# Enclosure_100x68_PBC-X.net
KiCad netlist of a schematic drawn in EAGLE
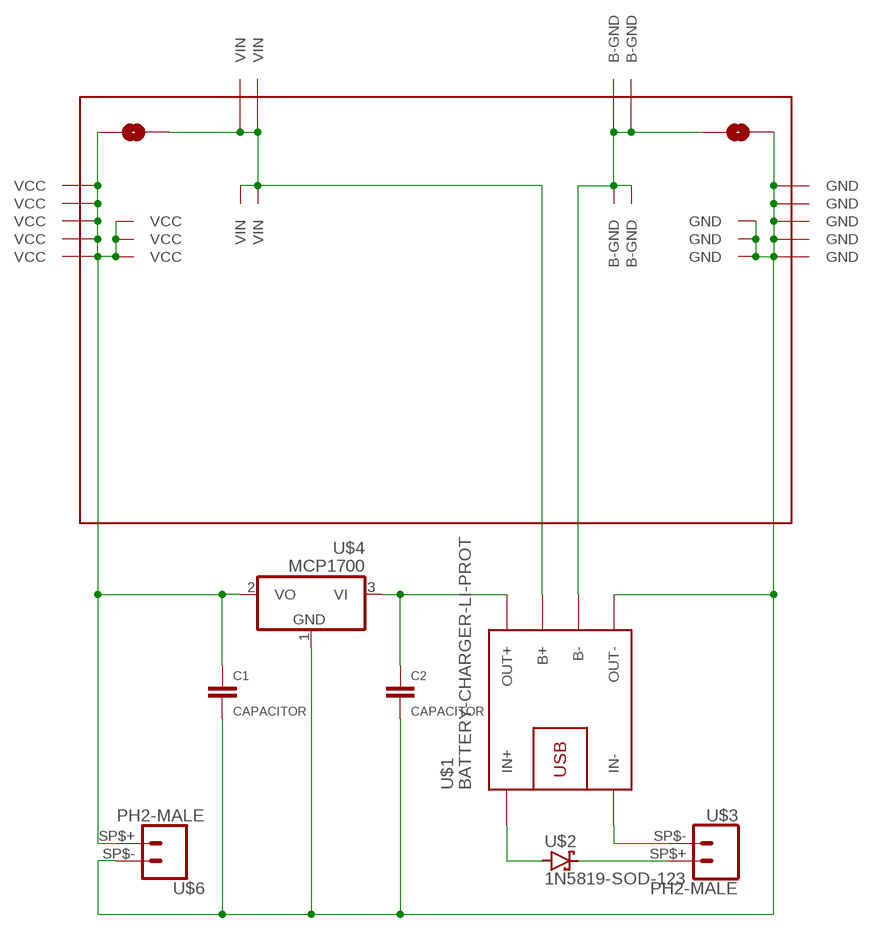
[diagram p0: schematic, sheet 1]

(export (version "E")
  (design (tool "Eeschema 10.0.6"))
  (components
    (comp (ref "C1")
      (value "CAPACITOR")
      (footprint "eagle-import:C0805")
      (libsource (lib "eagle-import") (part "CAPACITOR"))
    )
    (comp (ref "C2")
      (value "CAPACITOR")
      (footprint "eagle-import:C0805")
      (libsource (lib "eagle-import") (part "CAPACITOR"))
    )
    (comp (ref "U$1")
      (value "BATTERY-CHARGER-LI-PROT")
      (footprint "eagle-import:BATTERY-CHARGER-LI-PROT")
      (libsource (lib "eagle-import") (part "BATTERY-CHARGER-LI-PROT"))
    )
    (comp (ref "U$2")
      (value "1N5819-SOD-123")
      (footprint "eagle-import:SOD-123")
      (libsource (lib "eagle-import") (part "1N5819-SOD-123"))
    )
    (comp (ref "U$3")
      (value "PH2-MALE")
      (footprint "eagle-import:PH2")
      (libsource (lib "eagle-import") (part "PH2-MALE"))
    )
    (comp (ref "U$4")
      (value "MCP1700")
      (footprint "eagle-import:SOT23")
      (libsource (lib "eagle-import") (part "MCP1700"))
    )
    (comp (ref "U$5")
      (value "PROTO-34X22-BAT-SJ-CHG")
      (footprint "eagle-import:PROTO-34X22-BAT-SJ-CHG")
      (libsource (lib "eagle-import") (part "PROTO-34X22-BAT-SJ-CHG"))
    )
    (comp (ref "U$6")
      (value "PH2-MALE")
      (footprint "eagle-import:PH2")
      (libsource (lib "eagle-import") (part "PH2-MALE"))
    )
  )
  (nets
    (net (code "1") (name "Net-(U$1-PadB+)") (class "Default")
      (node (ref "U$1") (pin "B+") (pinfunction "B+_B+") (pintype "bidirectional"))
      (node (ref "U$5") (pin "P02-17") (pinfunction "VIN_P02-17") (pintype "power_in"))
      (node (ref "U$5") (pin "P03-16") (pinfunction "VIN_P03-16") (pintype "power_in"))
      (node (ref "U$5") (pin "P05-19") (pinfunction "VIN_P05-19") (pintype "power_in"))
      (node (ref "U$5") (pin "P06-19") (pinfunction "VIN_P06-19") (pintype "power_in"))
      (node (ref "U$5") (pin "VIN") (pinfunction "VIN_VIN") (pintype "power_in"))
    )
    (net (code "2") (name "Net-(U$1-PadB-)") (class "Default")
      (node (ref "U$1") (pin "B-") (pinfunction "B-_B-") (pintype "bidirectional"))
      (node (ref "U$5") (pin "B-GND") (pinfunction "B-GND_B-GND") (pintype "power_in"))
      (node (ref "U$5") (pin "P28-19") (pinfunction "B-GND_P28-19") (pintype "power_in"))
      (node (ref "U$5") (pin "P30-19") (pinfunction "B-GND_P30-19") (pintype "power_in"))
      (node (ref "U$5") (pin "P32-16") (pinfunction "B-GND_P32-16") (pintype "power_in"))
      (node (ref "U$5") (pin "P33-17") (pinfunction "B-GND_P33-17") (pintype "power_in"))
    )
    (net (code "3") (name "Net-(U$2-A)") (class "Default")
      (node (ref "U$1") (pin "IN+") (pinfunction "IN+_IN+") (pintype "bidirectional"))
      (node (ref "U$2") (pin "1") (pinfunction "A_1") (pintype "passive"))
    )
    (net (code "4") (name "Net-(U$2-C)") (class "Default")
      (node (ref "U$2") (pin "2") (pinfunction "C_2") (pintype "passive"))
      (node (ref "U$3") (pin "SP$+") (pinfunction "1_SP$+") (pintype "power_in"))
    )
    (net (code "5") (name "Net-(U$3-2)") (class "Default")
      (node (ref "U$1") (pin "IN-") (pinfunction "IN-_IN-") (pintype "bidirectional"))
      (node (ref "U$3") (pin "SP$-") (pinfunction "2_SP$-") (pintype "power_in"))
    )
    (net (code "6") (name "Net-(U$4-GND)") (class "Default")
      (node (ref "C1") (pin "2") (pinfunction "2_2") (pintype "passive"))
      (node (ref "C2") (pin "2") (pinfunction "2_2") (pintype "passive"))
      (node (ref "U$1") (pin "OUT-") (pinfunction "OUT-_OUT-") (pintype "bidirectional"))
      (node (ref "U$4") (pin "1") (pinfunction "GND_1") (pintype "passive"))
      (node (ref "U$5") (pin "GND") (pinfunction "GND_GND") (pintype "power_in"))
      (node (ref "U$5") (pin "P33-13") (pinfunction "GND_P33-13") (pintype "power_in"))
      (node (ref "U$5") (pin "P33-14") (pinfunction "GND_P33-14") (pintype "power_in"))
      (node (ref "U$5") (pin "P33-15") (pinfunction "GND_P33-15") (pintype "power_in"))
      (node (ref "U$5") (pin "P34-13") (pinfunction "GND_P34-13") (pintype "power_in"))
      (node (ref "U$5") (pin "P34-14") (pinfunction "GND_P34-14") (pintype "power_in"))
      (node (ref "U$5") (pin "P34-15") (pinfunction "GND_P34-15") (pintype "power_in"))
      (node (ref "U$5") (pin "P34-16") (pinfunction "GND_P34-16") (pintype "power_in"))
      (node (ref "U$5") (pin "P34-17") (pinfunction "GND_P34-17") (pintype "power_in"))
      (node (ref "U$6") (pin "SP$-") (pinfunction "2_SP$-") (pintype "power_in"))
    )
    (net (code "7") (name "Net-(U$4-VI)") (class "Default")
      (node (ref "C2") (pin "1") (pinfunction "1_1") (pintype "passive"))
      (node (ref "U$1") (pin "OUT+") (pinfunction "OUT+_OUT+") (pintype "bidirectional"))
      (node (ref "U$4") (pin "3") (pinfunction "VI_3") (pintype "input"))
    )
    (net (code "8") (name "Net-(U$4-VO)") (class "Default")
      (node (ref "C1") (pin "1") (pinfunction "1_1") (pintype "passive"))
      (node (ref "U$4") (pin "2") (pinfunction "VO_2") (pintype "output"))
      (node (ref "U$5") (pin "P01-13") (pinfunction "VCC_P01-13") (pintype "power_in"))
      (node (ref "U$5") (pin "P01-14") (pinfunction "VCC_P01-14") (pintype "power_in"))
      (node (ref "U$5") (pin "P01-15") (pinfunction "VCC_P01-15") (pintype "power_in"))
      (node (ref "U$5") (pin "P01-16") (pinfunction "VCC_P01-16") (pintype "power_in"))
      (node (ref "U$5") (pin "P01-17") (pinfunction "VCC_P01-17") (pintype "power_in"))
      (node (ref "U$5") (pin "P02-13") (pinfunction "VCC_P02-13") (pintype "power_in"))
      (node (ref "U$5") (pin "P02-14") (pinfunction "VCC_P02-14") (pintype "power_in"))
      (node (ref "U$5") (pin "P02-15") (pinfunction "VCC_P02-15") (pintype "power_in"))
      (node (ref "U$5") (pin "VCC") (pinfunction "VCC_VCC") (pintype "power_in"))
      (node (ref "U$6") (pin "SP$+") (pinfunction "1_SP$+") (pintype "power_in"))
    )
  )
)
